# GT-2022-001.net
KiCad netlist of a schematic drawn in EAGLE
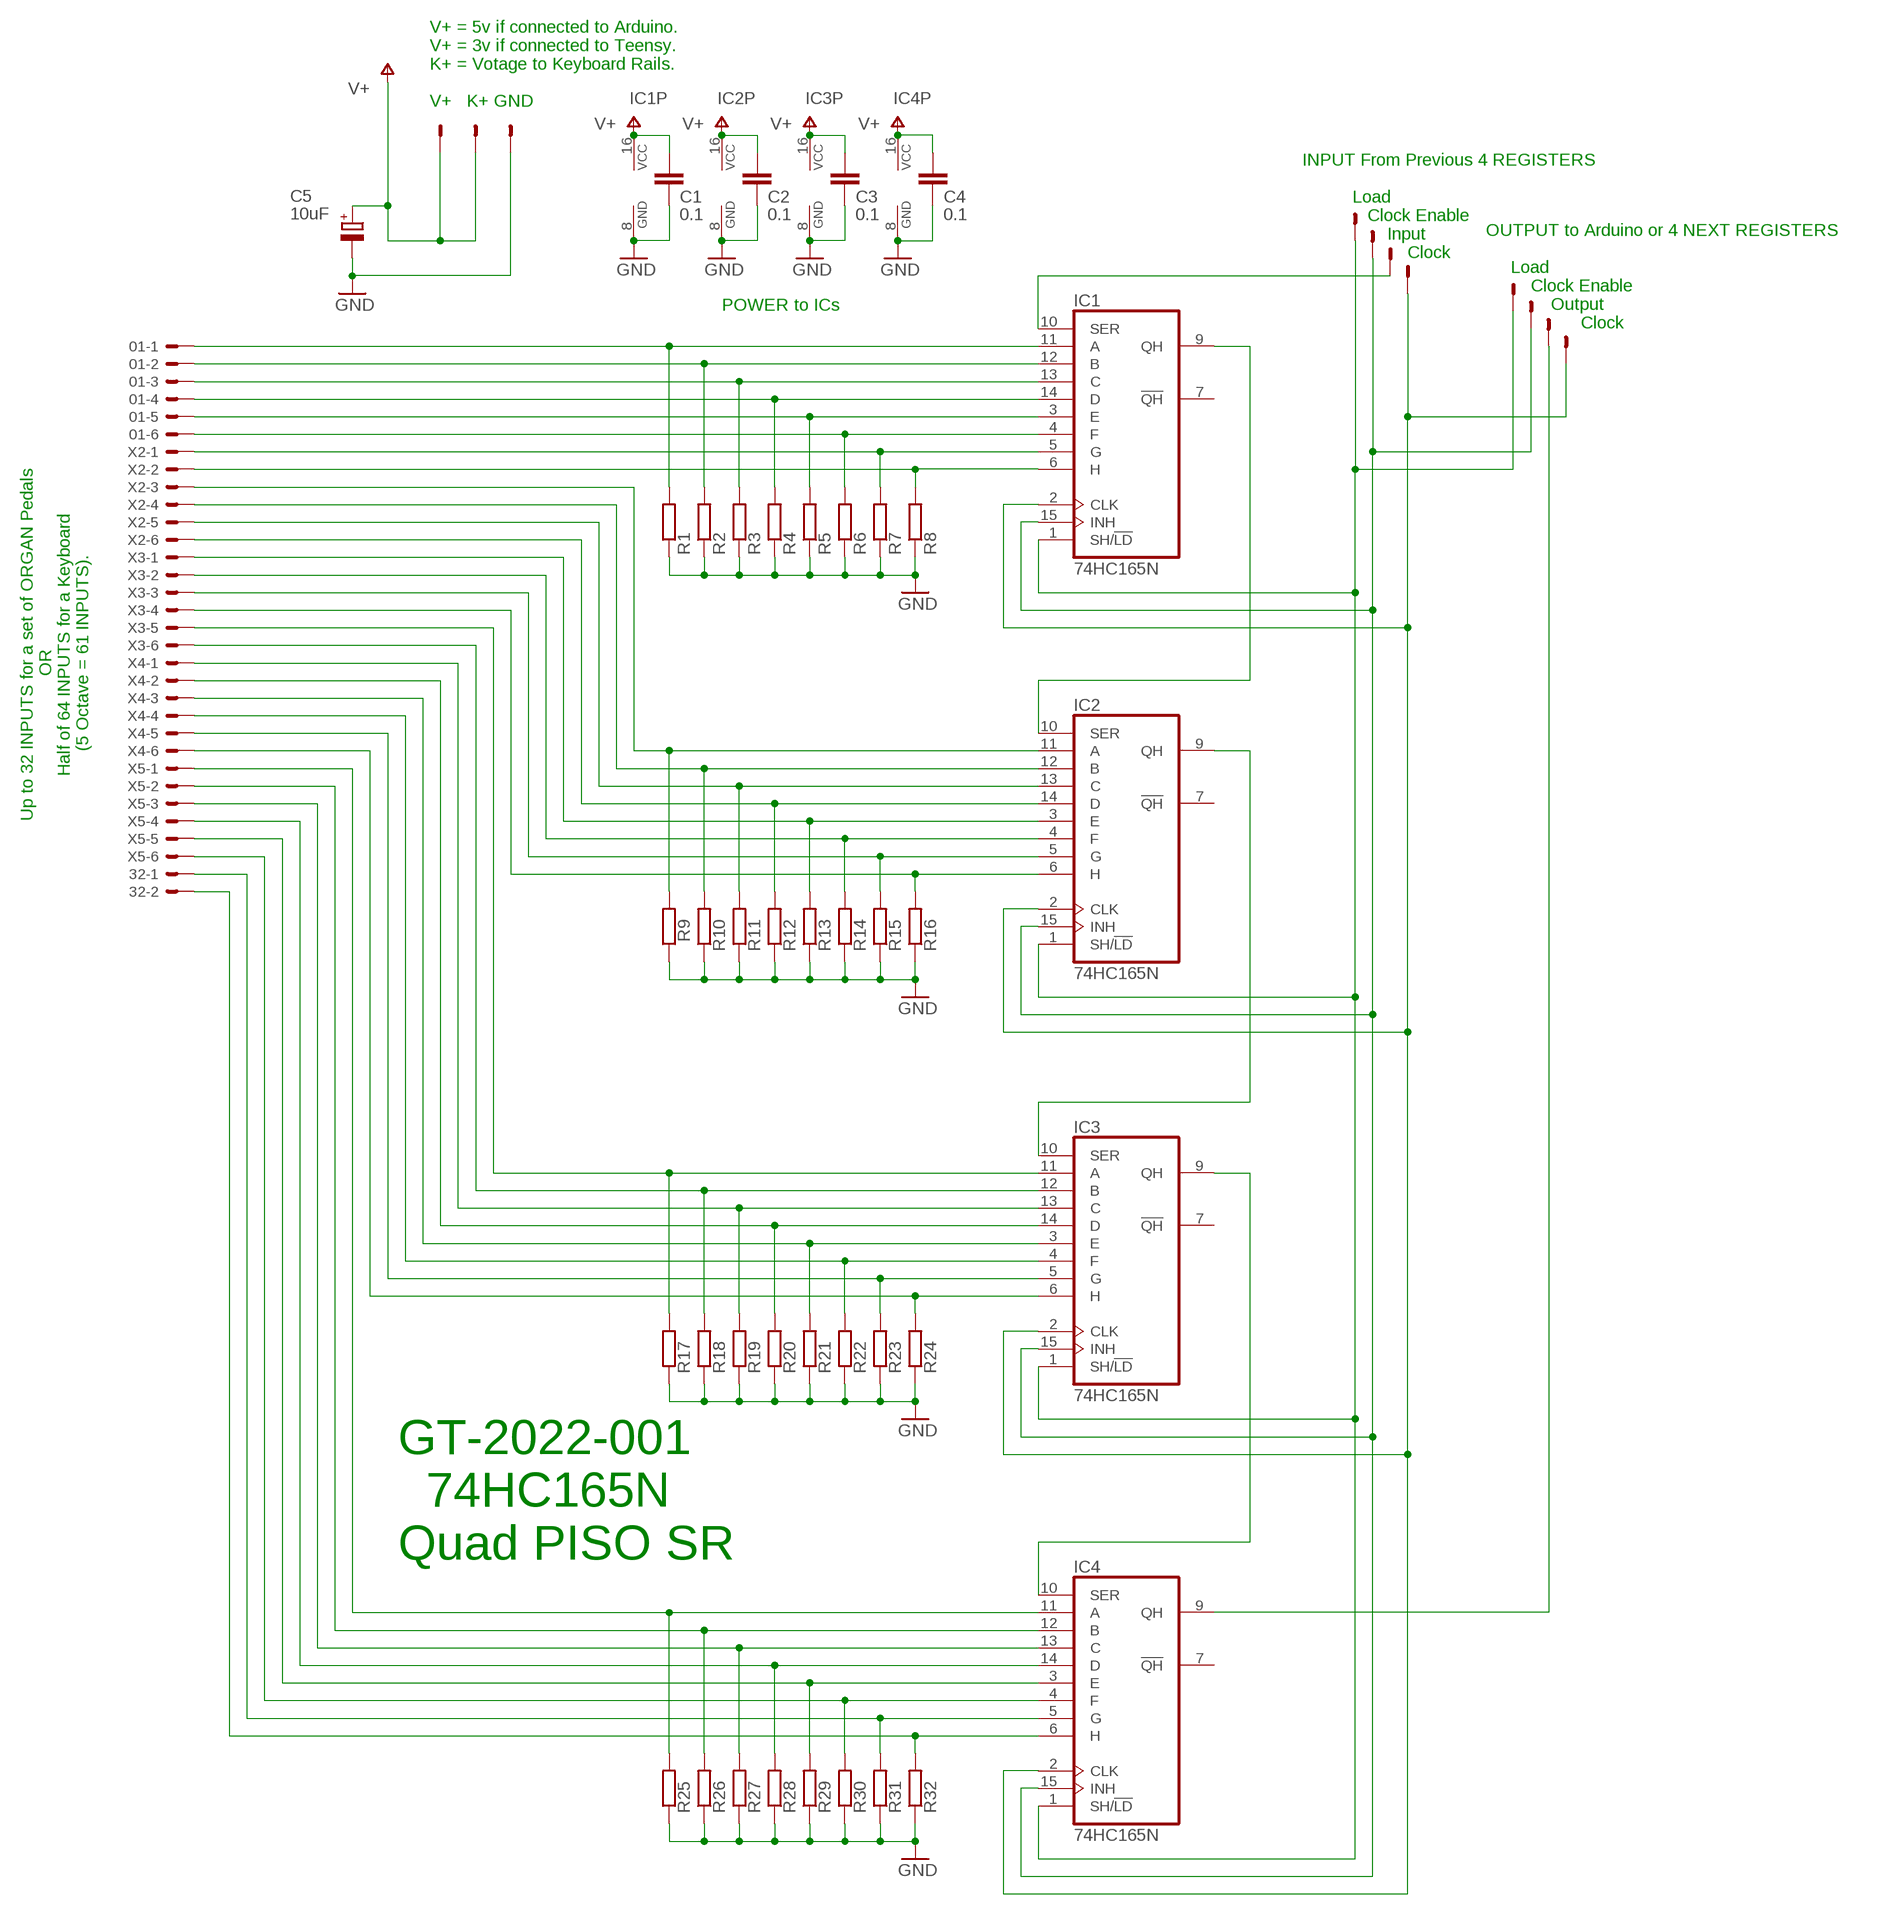
[diagram p0: schematic, sheet 1]

(export (version "E")
  (design (tool "Eeschema 10.0.6"))
  (components
    (comp (ref "01")
      (value "22-23-2061")
      (footprint "eagle-import:22-23-2061")
      (fields (field (name "MF") "MOLEX"))
      (libsource (lib "eagle-import") (part "22-23-2061"))
    )
    (comp (ref "32")
      (value "22-23-2021")
      (footprint "eagle-import:22-23-2021")
      (fields (field (name "MF") "MOLEX"))
      (libsource (lib "eagle-import") (part "22-23-2021"))
    )
    (comp (ref "C1")
      (value "0.1")
      (footprint "eagle-import:C025-025X050")
      (libsource (lib "eagle-import") (part "C-EU025-025X050"))
    )
    (comp (ref "C2")
      (value "0.1")
      (footprint "eagle-import:C025-025X050")
      (libsource (lib "eagle-import") (part "C-EU025-025X050"))
    )
    (comp (ref "C3")
      (value "0.1")
      (footprint "eagle-import:C025-025X050")
      (libsource (lib "eagle-import") (part "C-EU025-025X050"))
    )
    (comp (ref "C4")
      (value "0.1")
      (footprint "eagle-import:C025-025X050")
      (libsource (lib "eagle-import") (part "C-EU025-025X050"))
    )
    (comp (ref "C5")
      (value "10uF")
      (footprint "eagle-import:E2,5-7")
      (libsource (lib "eagle-import") (part "CPOL-EUE2.5-7"))
    )
    (comp (ref "IC1")
      (value "74HC165N")
      (footprint "eagle-import:DIL16")
      (libsource (lib "eagle-import") (part "74165NHC"))
    )
    (comp (ref "IC2")
      (value "74HC165N")
      (footprint "eagle-import:DIL16")
      (libsource (lib "eagle-import") (part "74165NHC"))
    )
    (comp (ref "IC3")
      (value "74HC165N")
      (footprint "eagle-import:DIL16")
      (libsource (lib "eagle-import") (part "74165NHC"))
    )
    (comp (ref "IC4")
      (value "74HC165N")
      (footprint "eagle-import:DIL16")
      (libsource (lib "eagle-import") (part "74165NHC"))
    )
    (comp (ref "LD_CE_IN_CK")
      (value "22-23-2041")
      (footprint "eagle-import:22-23-2041")
      (fields (field (name "MF") "MOLEX"))
      (libsource (lib "eagle-import") (part "22-23-2041"))
    )
    (comp (ref "LD_CE_OUT_CLK")
      (value "22-23-2041")
      (footprint "eagle-import:22-23-2041")
      (fields (field (name "MF") "MOLEX"))
      (libsource (lib "eagle-import") (part "22-23-2041"))
    )
    (comp (ref "R1")
      (value "R-EU_0204/7")
      (footprint "eagle-import:0204_7")
      (libsource (lib "eagle-import") (part "R-EU_0204/7"))
    )
    (comp (ref "R2")
      (value "R-EU_0204/7")
      (footprint "eagle-import:0204_7")
      (libsource (lib "eagle-import") (part "R-EU_0204/7"))
    )
    (comp (ref "R3")
      (value "R-EU_0204/7")
      (footprint "eagle-import:0204_7")
      (libsource (lib "eagle-import") (part "R-EU_0204/7"))
    )
    (comp (ref "R4")
      (value "R-EU_0204/7")
      (footprint "eagle-import:0204_7")
      (libsource (lib "eagle-import") (part "R-EU_0204/7"))
    )
    (comp (ref "R5")
      (value "R-EU_0204/7")
      (footprint "eagle-import:0204_7")
      (libsource (lib "eagle-import") (part "R-EU_0204/7"))
    )
    (comp (ref "R6")
      (value "R-EU_0204/7")
      (footprint "eagle-import:0204_7")
      (libsource (lib "eagle-import") (part "R-EU_0204/7"))
    )
    (comp (ref "R7")
      (value "R-EU_0204/7")
      (footprint "eagle-import:0204_7")
      (libsource (lib "eagle-import") (part "R-EU_0204/7"))
    )
    (comp (ref "R8")
      (value "R-EU_0204/7")
      (footprint "eagle-import:0204_7")
      (libsource (lib "eagle-import") (part "R-EU_0204/7"))
    )
    (comp (ref "R9")
      (value "R-EU_0204/7")
      (footprint "eagle-import:0204_7")
      (libsource (lib "eagle-import") (part "R-EU_0204/7"))
    )
    (comp (ref "R10")
      (value "R-EU_0204/7")
      (footprint "eagle-import:0204_7")
      (libsource (lib "eagle-import") (part "R-EU_0204/7"))
    )
    (comp (ref "R11")
      (value "R-EU_0204/7")
      (footprint "eagle-import:0204_7")
      (libsource (lib "eagle-import") (part "R-EU_0204/7"))
    )
    (comp (ref "R12")
      (value "R-EU_0204/7")
      (footprint "eagle-import:0204_7")
      (libsource (lib "eagle-import") (part "R-EU_0204/7"))
    )
    (comp (ref "R13")
      (value "R-EU_0204/7")
      (footprint "eagle-import:0204_7")
      (libsource (lib "eagle-import") (part "R-EU_0204/7"))
    )
    (comp (ref "R14")
      (value "R-EU_0204/7")
      (footprint "eagle-import:0204_7")
      (libsource (lib "eagle-import") (part "R-EU_0204/7"))
    )
    (comp (ref "R15")
      (value "R-EU_0204/7")
      (footprint "eagle-import:0204_7")
      (libsource (lib "eagle-import") (part "R-EU_0204/7"))
    )
    (comp (ref "R16")
      (value "R-EU_0204/7")
      (footprint "eagle-import:0204_7")
      (libsource (lib "eagle-import") (part "R-EU_0204/7"))
    )
    (comp (ref "R17")
      (value "R-EU_0204/7")
      (footprint "eagle-import:0204_7")
      (libsource (lib "eagle-import") (part "R-EU_0204/7"))
    )
    (comp (ref "R18")
      (value "R-EU_0204/7")
      (footprint "eagle-import:0204_7")
      (libsource (lib "eagle-import") (part "R-EU_0204/7"))
    )
    (comp (ref "R19")
      (value "R-EU_0204/7")
      (footprint "eagle-import:0204_7")
      (libsource (lib "eagle-import") (part "R-EU_0204/7"))
    )
    (comp (ref "R20")
      (value "R-EU_0204/7")
      (footprint "eagle-import:0204_7")
      (libsource (lib "eagle-import") (part "R-EU_0204/7"))
    )
    (comp (ref "R21")
      (value "R-EU_0204/7")
      (footprint "eagle-import:0204_7")
      (libsource (lib "eagle-import") (part "R-EU_0204/7"))
    )
    (comp (ref "R22")
      (value "R-EU_0204/7")
      (footprint "eagle-import:0204_7")
      (libsource (lib "eagle-import") (part "R-EU_0204/7"))
    )
    (comp (ref "R23")
      (value "R-EU_0204/7")
      (footprint "eagle-import:0204_7")
      (libsource (lib "eagle-import") (part "R-EU_0204/7"))
    )
    (comp (ref "R24")
      (value "R-EU_0204/7")
      (footprint "eagle-import:0204_7")
      (libsource (lib "eagle-import") (part "R-EU_0204/7"))
    )
    (comp (ref "R25")
      (value "R-EU_0204/7")
      (footprint "eagle-import:0204_7")
      (libsource (lib "eagle-import") (part "R-EU_0204/7"))
    )
    (comp (ref "R26")
      (value "R-EU_0204/7")
      (footprint "eagle-import:0204_7")
      (libsource (lib "eagle-import") (part "R-EU_0204/7"))
    )
    (comp (ref "R27")
      (value "R-EU_0204/7")
      (footprint "eagle-import:0204_7")
      (libsource (lib "eagle-import") (part "R-EU_0204/7"))
    )
    (comp (ref "R28")
      (value "R-EU_0204/7")
      (footprint "eagle-import:0204_7")
      (libsource (lib "eagle-import") (part "R-EU_0204/7"))
    )
    (comp (ref "R29")
      (value "R-EU_0204/7")
      (footprint "eagle-import:0204_7")
      (libsource (lib "eagle-import") (part "R-EU_0204/7"))
    )
    (comp (ref "R30")
      (value "R-EU_0204/7")
      (footprint "eagle-import:0204_7")
      (libsource (lib "eagle-import") (part "R-EU_0204/7"))
    )
    (comp (ref "R31")
      (value "R-EU_0204/7")
      (footprint "eagle-import:0204_7")
      (libsource (lib "eagle-import") (part "R-EU_0204/7"))
    )
    (comp (ref "R32")
      (value "R-EU_0204/7")
      (footprint "eagle-import:0204_7")
      (libsource (lib "eagle-import") (part "R-EU_0204/7"))
    )
    (comp (ref "V+_K+_GND")
      (value "22-23-2031")
      (footprint "eagle-import:22-23-2031")
      (fields (field (name "MF") "MOLEX"))
      (libsource (lib "eagle-import") (part "22-23-2031"))
    )
    (comp (ref "X2")
      (value "22-23-2061")
      (footprint "eagle-import:22-23-2061")
      (fields (field (name "MF") "MOLEX"))
      (libsource (lib "eagle-import") (part "22-23-2061"))
    )
    (comp (ref "X3")
      (value "22-23-2061")
      (footprint "eagle-import:22-23-2061")
      (fields (field (name "MF") "MOLEX"))
      (libsource (lib "eagle-import") (part "22-23-2061"))
    )
    (comp (ref "X4")
      (value "22-23-2061")
      (footprint "eagle-import:22-23-2061")
      (fields (field (name "MF") "MOLEX"))
      (libsource (lib "eagle-import") (part "22-23-2061"))
    )
    (comp (ref "X5")
      (value "22-23-2061")
      (footprint "eagle-import:22-23-2061")
      (fields (field (name "MF") "MOLEX"))
      (libsource (lib "eagle-import") (part "22-23-2061"))
    )
  )
  (nets
    (net (code "1") (name "GND") (class "Default")
      (node (ref "C1") (pin "2") (pinfunction "2_2") (pintype "passive"))
      (node (ref "C2") (pin "2") (pinfunction "2_2") (pintype "passive"))
      (node (ref "C3") (pin "2") (pinfunction "2_2") (pintype "passive"))
      (node (ref "C4") (pin "2") (pinfunction "2_2") (pintype "passive"))
      (node (ref "C5") (pin "-") (pinfunction "-_-") (pintype "passive"))
      (node (ref "IC1") (pin "8") (pinfunction "GND_8") (pintype "power_in"))
      (node (ref "IC2") (pin "8") (pinfunction "GND_8") (pintype "power_in"))
      (node (ref "IC3") (pin "8") (pinfunction "GND_8") (pintype "power_in"))
      (node (ref "IC4") (pin "8") (pinfunction "GND_8") (pintype "power_in"))
      (node (ref "R1") (pin "1") (pinfunction "1_1") (pintype "passive"))
      (node (ref "R10") (pin "1") (pinfunction "1_1") (pintype "passive"))
      (node (ref "R11") (pin "1") (pinfunction "1_1") (pintype "passive"))
      (node (ref "R12") (pin "1") (pinfunction "1_1") (pintype "passive"))
      (node (ref "R13") (pin "1") (pinfunction "1_1") (pintype "passive"))
      (node (ref "R14") (pin "1") (pinfunction "1_1") (pintype "passive"))
      (node (ref "R15") (pin "1") (pinfunction "1_1") (pintype "passive"))
      (node (ref "R16") (pin "1") (pinfunction "1_1") (pintype "passive"))
      (node (ref "R17") (pin "1") (pinfunction "1_1") (pintype "passive"))
      (node (ref "R18") (pin "1") (pinfunction "1_1") (pintype "passive"))
      (node (ref "R19") (pin "1") (pinfunction "1_1") (pintype "passive"))
      (node (ref "R2") (pin "1") (pinfunction "1_1") (pintype "passive"))
      (node (ref "R20") (pin "1") (pinfunction "1_1") (pintype "passive"))
      (node (ref "R21") (pin "1") (pinfunction "1_1") (pintype "passive"))
      (node (ref "R22") (pin "1") (pinfunction "1_1") (pintype "passive"))
      (node (ref "R23") (pin "1") (pinfunction "1_1") (pintype "passive"))
      (node (ref "R24") (pin "1") (pinfunction "1_1") (pintype "passive"))
      (node (ref "R25") (pin "1") (pinfunction "1_1") (pintype "passive"))
      (node (ref "R26") (pin "1") (pinfunction "1_1") (pintype "passive"))
      (node (ref "R27") (pin "1") (pinfunction "1_1") (pintype "passive"))
      (node (ref "R28") (pin "1") (pinfunction "1_1") (pintype "passive"))
      (node (ref "R29") (pin "1") (pinfunction "1_1") (pintype "passive"))
      (node (ref "R3") (pin "1") (pinfunction "1_1") (pintype "passive"))
      (node (ref "R30") (pin "1") (pinfunction "1_1") (pintype "passive"))
      (node (ref "R31") (pin "1") (pinfunction "1_1") (pintype "passive"))
      (node (ref "R32") (pin "1") (pinfunction "1_1") (pintype "passive"))
      (node (ref "R4") (pin "1") (pinfunction "1_1") (pintype "passive"))
      (node (ref "R5") (pin "1") (pinfunction "1_1") (pintype "passive"))
      (node (ref "R6") (pin "1") (pinfunction "1_1") (pintype "passive"))
      (node (ref "R7") (pin "1") (pinfunction "1_1") (pintype "passive"))
      (node (ref "R8") (pin "1") (pinfunction "1_1") (pintype "passive"))
      (node (ref "R9") (pin "1") (pinfunction "1_1") (pintype "passive"))
      (node (ref "V+_K+_GND") (pin "3") (pinfunction "S_3") (pintype "passive"))
    )
    (net (code "2") (name "Net-(01A-S)") (class "Default")
      (node (ref "01") (pin "1") (pinfunction "S_1") (pintype "passive"))
      (node (ref "IC1") (pin "11") (pinfunction "A_11") (pintype "input"))
      (node (ref "R1") (pin "2") (pinfunction "2_2") (pintype "passive"))
    )
    (net (code "3") (name "Net-(01B-S)") (class "Default")
      (node (ref "01") (pin "2") (pinfunction "S_2") (pintype "passive"))
      (node (ref "IC1") (pin "12") (pinfunction "B_12") (pintype "input"))
      (node (ref "R2") (pin "2") (pinfunction "2_2") (pintype "passive"))
    )
    (net (code "4") (name "Net-(01C-S)") (class "Default")
      (node (ref "01") (pin "3") (pinfunction "S_3") (pintype "passive"))
      (node (ref "IC1") (pin "13") (pinfunction "C_13") (pintype "input"))
      (node (ref "R3") (pin "2") (pinfunction "2_2") (pintype "passive"))
    )
    (net (code "5") (name "Net-(01D-S)") (class "Default")
      (node (ref "01") (pin "4") (pinfunction "S_4") (pintype "passive"))
      (node (ref "IC1") (pin "14") (pinfunction "D_14") (pintype "input"))
      (node (ref "R4") (pin "2") (pinfunction "2_2") (pintype "passive"))
    )
    (net (code "6") (name "Net-(01E-S)") (class "Default")
      (node (ref "01") (pin "5") (pinfunction "S_5") (pintype "passive"))
      (node (ref "IC1") (pin "3") (pinfunction "E_3") (pintype "input"))
      (node (ref "R5") (pin "2") (pinfunction "2_2") (pintype "passive"))
    )
    (net (code "7") (name "Net-(01F-S)") (class "Default")
      (node (ref "01") (pin "6") (pinfunction "S_6") (pintype "passive"))
      (node (ref "IC1") (pin "4") (pinfunction "F_4") (pintype "input"))
      (node (ref "R6") (pin "2") (pinfunction "2_2") (pintype "passive"))
    )
    (net (code "8") (name "Net-(32A-S)") (class "Default")
      (node (ref "32") (pin "1") (pinfunction "S_1") (pintype "passive"))
      (node (ref "IC4") (pin "5") (pinfunction "G_5") (pintype "input"))
      (node (ref "R31") (pin "2") (pinfunction "2_2") (pintype "passive"))
    )
    (net (code "9") (name "Net-(32B-S)") (class "Default")
      (node (ref "32") (pin "2") (pinfunction "S_2") (pintype "passive"))
      (node (ref "IC4") (pin "6") (pinfunction "H_6") (pintype "input"))
      (node (ref "R32") (pin "2") (pinfunction "2_2") (pintype "passive"))
    )
    (net (code "10") (name "Net-(IC1A-CLK)") (class "Default")
      (node (ref "IC1") (pin "2") (pinfunction "CLK_2") (pintype "input"))
      (node (ref "IC2") (pin "2") (pinfunction "CLK_2") (pintype "input"))
      (node (ref "IC3") (pin "2") (pinfunction "CLK_2") (pintype "input"))
      (node (ref "IC4") (pin "2") (pinfunction "CLK_2") (pintype "input"))
      (node (ref "LD_CE_IN_CK") (pin "4") (pinfunction "S_4") (pintype "passive"))
      (node (ref "LD_CE_OUT_CLK") (pin "4") (pinfunction "S_4") (pintype "passive"))
    )
    (net (code "11") (name "Net-(IC1A-G)") (class "Default")
      (node (ref "IC1") (pin "5") (pinfunction "G_5") (pintype "input"))
      (node (ref "R7") (pin "2") (pinfunction "2_2") (pintype "passive"))
      (node (ref "X2") (pin "1") (pinfunction "S_1") (pintype "passive"))
    )
    (net (code "12") (name "Net-(IC1A-H)") (class "Default")
      (node (ref "IC1") (pin "6") (pinfunction "H_6") (pintype "input"))
      (node (ref "R8") (pin "2") (pinfunction "2_2") (pintype "passive"))
      (node (ref "X2") (pin "2") (pinfunction "S_2") (pintype "passive"))
    )
    (net (code "13") (name "Net-(IC1A-INH)") (class "Default")
      (node (ref "IC1") (pin "15") (pinfunction "INH_15") (pintype "input"))
      (node (ref "IC2") (pin "15") (pinfunction "INH_15") (pintype "input"))
      (node (ref "IC3") (pin "15") (pinfunction "INH_15") (pintype "input"))
      (node (ref "IC4") (pin "15") (pinfunction "INH_15") (pintype "input"))
      (node (ref "LD_CE_IN_CK") (pin "2") (pinfunction "S_2") (pintype "passive"))
      (node (ref "LD_CE_OUT_CLK") (pin "2") (pinfunction "S_2") (pintype "passive"))
    )
    (net (code "14") (name "Net-(IC1A-QH)") (class "Default")
      (node (ref "IC1") (pin "9") (pinfunction "QH_9") (pintype "output"))
      (node (ref "IC2") (pin "10") (pinfunction "SER_10") (pintype "input"))
    )
    (net (code "15") (name "Net-(IC1A-SER)") (class "Default")
      (node (ref "IC1") (pin "10") (pinfunction "SER_10") (pintype "input"))
      (node (ref "LD_CE_IN_CK") (pin "3") (pinfunction "S_3") (pintype "passive"))
    )
    (net (code "16") (name "Net-(IC1A-SH{slash}~{LD})") (class "Default")
      (node (ref "IC1") (pin "1") (pinfunction "SH/~{LD}_1") (pintype "input"))
      (node (ref "IC2") (pin "1") (pinfunction "SH/~{LD}_1") (pintype "input"))
      (node (ref "IC3") (pin "1") (pinfunction "SH/~{LD}_1") (pintype "input"))
      (node (ref "IC4") (pin "1") (pinfunction "SH/~{LD}_1") (pintype "input"))
      (node (ref "LD_CE_IN_CK") (pin "1") (pinfunction "S_1") (pintype "passive"))
      (node (ref "LD_CE_OUT_CLK") (pin "1") (pinfunction "S_1") (pintype "passive"))
    )
    (net (code "17") (name "Net-(IC2A-A)") (class "Default")
      (node (ref "IC2") (pin "11") (pinfunction "A_11") (pintype "input"))
      (node (ref "R9") (pin "2") (pinfunction "2_2") (pintype "passive"))
      (node (ref "X2") (pin "3") (pinfunction "S_3") (pintype "passive"))
    )
    (net (code "18") (name "Net-(IC2A-B)") (class "Default")
      (node (ref "IC2") (pin "12") (pinfunction "B_12") (pintype "input"))
      (node (ref "R10") (pin "2") (pinfunction "2_2") (pintype "passive"))
      (node (ref "X2") (pin "4") (pinfunction "S_4") (pintype "passive"))
    )
    (net (code "19") (name "Net-(IC2A-C)") (class "Default")
      (node (ref "IC2") (pin "13") (pinfunction "C_13") (pintype "input"))
      (node (ref "R11") (pin "2") (pinfunction "2_2") (pintype "passive"))
      (node (ref "X2") (pin "5") (pinfunction "S_5") (pintype "passive"))
    )
    (net (code "20") (name "Net-(IC2A-D)") (class "Default")
      (node (ref "IC2") (pin "14") (pinfunction "D_14") (pintype "input"))
      (node (ref "R12") (pin "2") (pinfunction "2_2") (pintype "passive"))
      (node (ref "X2") (pin "6") (pinfunction "S_6") (pintype "passive"))
    )
    (net (code "21") (name "Net-(IC2A-E)") (class "Default")
      (node (ref "IC2") (pin "3") (pinfunction "E_3") (pintype "input"))
      (node (ref "R13") (pin "2") (pinfunction "2_2") (pintype "passive"))
      (node (ref "X3") (pin "1") (pinfunction "S_1") (pintype "passive"))
    )
    (net (code "22") (name "Net-(IC2A-F)") (class "Default")
      (node (ref "IC2") (pin "4") (pinfunction "F_4") (pintype "input"))
      (node (ref "R14") (pin "2") (pinfunction "2_2") (pintype "passive"))
      (node (ref "X3") (pin "2") (pinfunction "S_2") (pintype "passive"))
    )
    (net (code "23") (name "Net-(IC2A-G)") (class "Default")
      (node (ref "IC2") (pin "5") (pinfunction "G_5") (pintype "input"))
      (node (ref "R15") (pin "2") (pinfunction "2_2") (pintype "passive"))
      (node (ref "X3") (pin "3") (pinfunction "S_3") (pintype "passive"))
    )
    (net (code "24") (name "Net-(IC2A-H)") (class "Default")
      (node (ref "IC2") (pin "6") (pinfunction "H_6") (pintype "input"))
      (node (ref "R16") (pin "2") (pinfunction "2_2") (pintype "passive"))
      (node (ref "X3") (pin "4") (pinfunction "S_4") (pintype "passive"))
    )
    (net (code "25") (name "Net-(IC2A-QH)") (class "Default")
      (node (ref "IC2") (pin "9") (pinfunction "QH_9") (pintype "output"))
      (node (ref "IC3") (pin "10") (pinfunction "SER_10") (pintype "input"))
    )
    (net (code "26") (name "Net-(IC3A-A)") (class "Default")
      (node (ref "IC3") (pin "11") (pinfunction "A_11") (pintype "input"))
      (node (ref "R17") (pin "2") (pinfunction "2_2") (pintype "passive"))
      (node (ref "X3") (pin "5") (pinfunction "S_5") (pintype "passive"))
    )
    (net (code "27") (name "Net-(IC3A-B)") (class "Default")
      (node (ref "IC3") (pin "12") (pinfunction "B_12") (pintype "input"))
      (node (ref "R18") (pin "2") (pinfunction "2_2") (pintype "passive"))
      (node (ref "X3") (pin "6") (pinfunction "S_6") (pintype "passive"))
    )
    (net (code "28") (name "Net-(IC3A-C)") (class "Default")
      (node (ref "IC3") (pin "13") (pinfunction "C_13") (pintype "input"))
      (node (ref "R19") (pin "2") (pinfunction "2_2") (pintype "passive"))
      (node (ref "X4") (pin "1") (pinfunction "S_1") (pintype "passive"))
    )
    (net (code "29") (name "Net-(IC3A-D)") (class "Default")
      (node (ref "IC3") (pin "14") (pinfunction "D_14") (pintype "input"))
      (node (ref "R20") (pin "2") (pinfunction "2_2") (pintype "passive"))
      (node (ref "X4") (pin "2") (pinfunction "S_2") (pintype "passive"))
    )
    (net (code "30") (name "Net-(IC3A-E)") (class "Default")
      (node (ref "IC3") (pin "3") (pinfunction "E_3") (pintype "input"))
      (node (ref "R21") (pin "2") (pinfunction "2_2") (pintype "passive"))
      (node (ref "X4") (pin "3") (pinfunction "S_3") (pintype "passive"))
    )
    (net (code "31") (name "Net-(IC3A-F)") (class "Default")
      (node (ref "IC3") (pin "4") (pinfunction "F_4") (pintype "input"))
      (node (ref "R22") (pin "2") (pinfunction "2_2") (pintype "passive"))
      (node (ref "X4") (pin "4") (pinfunction "S_4") (pintype "passive"))
    )
    (net (code "32") (name "Net-(IC3A-G)") (class "Default")
      (node (ref "IC3") (pin "5") (pinfunction "G_5") (pintype "input"))
      (node (ref "R23") (pin "2") (pinfunction "2_2") (pintype "passive"))
      (node (ref "X4") (pin "5") (pinfunction "S_5") (pintype "passive"))
    )
    (net (code "33") (name "Net-(IC3A-H)") (class "Default")
      (node (ref "IC3") (pin "6") (pinfunction "H_6") (pintype "input"))
      (node (ref "R24") (pin "2") (pinfunction "2_2") (pintype "passive"))
      (node (ref "X4") (pin "6") (pinfunction "S_6") (pintype "passive"))
    )
    (net (code "34") (name "Net-(IC3A-QH)") (class "Default")
      (node (ref "IC3") (pin "9") (pinfunction "QH_9") (pintype "output"))
      (node (ref "IC4") (pin "10") (pinfunction "SER_10") (pintype "input"))
    )
    (net (code "35") (name "Net-(IC4A-A)") (class "Default")
      (node (ref "IC4") (pin "11") (pinfunction "A_11") (pintype "input"))
      (node (ref "R25") (pin "2") (pinfunction "2_2") (pintype "passive"))
      (node (ref "X5") (pin "1") (pinfunction "S_1") (pintype "passive"))
    )
    (net (code "36") (name "Net-(IC4A-B)") (class "Default")
      (node (ref "IC4") (pin "12") (pinfunction "B_12") (pintype "input"))
      (node (ref "R26") (pin "2") (pinfunction "2_2") (pintype "passive"))
      (node (ref "X5") (pin "2") (pinfunction "S_2") (pintype "passive"))
    )
    (net (code "37") (name "Net-(IC4A-C)") (class "Default")
      (node (ref "IC4") (pin "13") (pinfunction "C_13") (pintype "input"))
      (node (ref "R27") (pin "2") (pinfunction "2_2") (pintype "passive"))
      (node (ref "X5") (pin "3") (pinfunction "S_3") (pintype "passive"))
    )
    (net (code "38") (name "Net-(IC4A-D)") (class "Default")
      (node (ref "IC4") (pin "14") (pinfunction "D_14") (pintype "input"))
      (node (ref "R28") (pin "2") (pinfunction "2_2") (pintype "passive"))
      (node (ref "X5") (pin "4") (pinfunction "S_4") (pintype "passive"))
    )
    (net (code "39") (name "Net-(IC4A-E)") (class "Default")
      (node (ref "IC4") (pin "3") (pinfunction "E_3") (pintype "input"))
      (node (ref "R29") (pin "2") (pinfunction "2_2") (pintype "passive"))
      (node (ref "X5") (pin "5") (pinfunction "S_5") (pintype "passive"))
    )
    (net (code "40") (name "Net-(IC4A-F)") (class "Default")
      (node (ref "IC4") (pin "4") (pinfunction "F_4") (pintype "input"))
      (node (ref "R30") (pin "2") (pinfunction "2_2") (pintype "passive"))
      (node (ref "X5") (pin "6") (pinfunction "S_6") (pintype "passive"))
    )
    (net (code "41") (name "Net-(IC4A-QH)") (class "Default")
      (node (ref "IC4") (pin "9") (pinfunction "QH_9") (pintype "output"))
      (node (ref "LD_CE_OUT_CLK") (pin "3") (pinfunction "S_3") (pintype "passive"))
    )
    (net (code "42") (name "V+") (class "Default")
      (node (ref "C1") (pin "1") (pinfunction "1_1") (pintype "passive"))
      (node (ref "C2") (pin "1") (pinfunction "1_1") (pintype "passive"))
      (node (ref "C3") (pin "1") (pinfunction "1_1") (pintype "passive"))
      (node (ref "C4") (pin "1") (pinfunction "1_1") (pintype "passive"))
      (node (ref "C5") (pin "+") (pinfunction "+_+") (pintype "passive"))
      (node (ref "IC1") (pin "16") (pinfunction "VCC_16") (pintype "power_in"))
      (node (ref "IC2") (pin "16") (pinfunction "VCC_16") (pintype "power_in"))
      (node (ref "IC3") (pin "16") (pinfunction "VCC_16") (pintype "power_in"))
      (node (ref "IC4") (pin "16") (pinfunction "VCC_16") (pintype "power_in"))
      (node (ref "V+_K+_GND") (pin "1") (pinfunction "S_1") (pintype "passive"))
      (node (ref "V+_K+_GND") (pin "2") (pinfunction "S_2") (pintype "passive"))
    )
    (net (code "43") (name "unconnected-(IC1A-~{QH}-Pad7)") (class "Default")
      (node (ref "IC1") (pin "7") (pinfunction "~{QH}_7") (pintype "output"))
    )
    (net (code "44") (name "unconnected-(IC2A-~{QH}-Pad7)") (class "Default")
      (node (ref "IC2") (pin "7") (pinfunction "~{QH}_7") (pintype "output"))
    )
    (net (code "45") (name "unconnected-(IC3A-~{QH}-Pad7)") (class "Default")
      (node (ref "IC3") (pin "7") (pinfunction "~{QH}_7") (pintype "output"))
    )
    (net (code "46") (name "unconnected-(IC4A-~{QH}-Pad7)") (class "Default")
      (node (ref "IC4") (pin "7") (pinfunction "~{QH}_7") (pintype "output"))
    )
  )
)
